# Smart_Assistant.net
KiCad netlist of a schematic drawn in Altium Designer
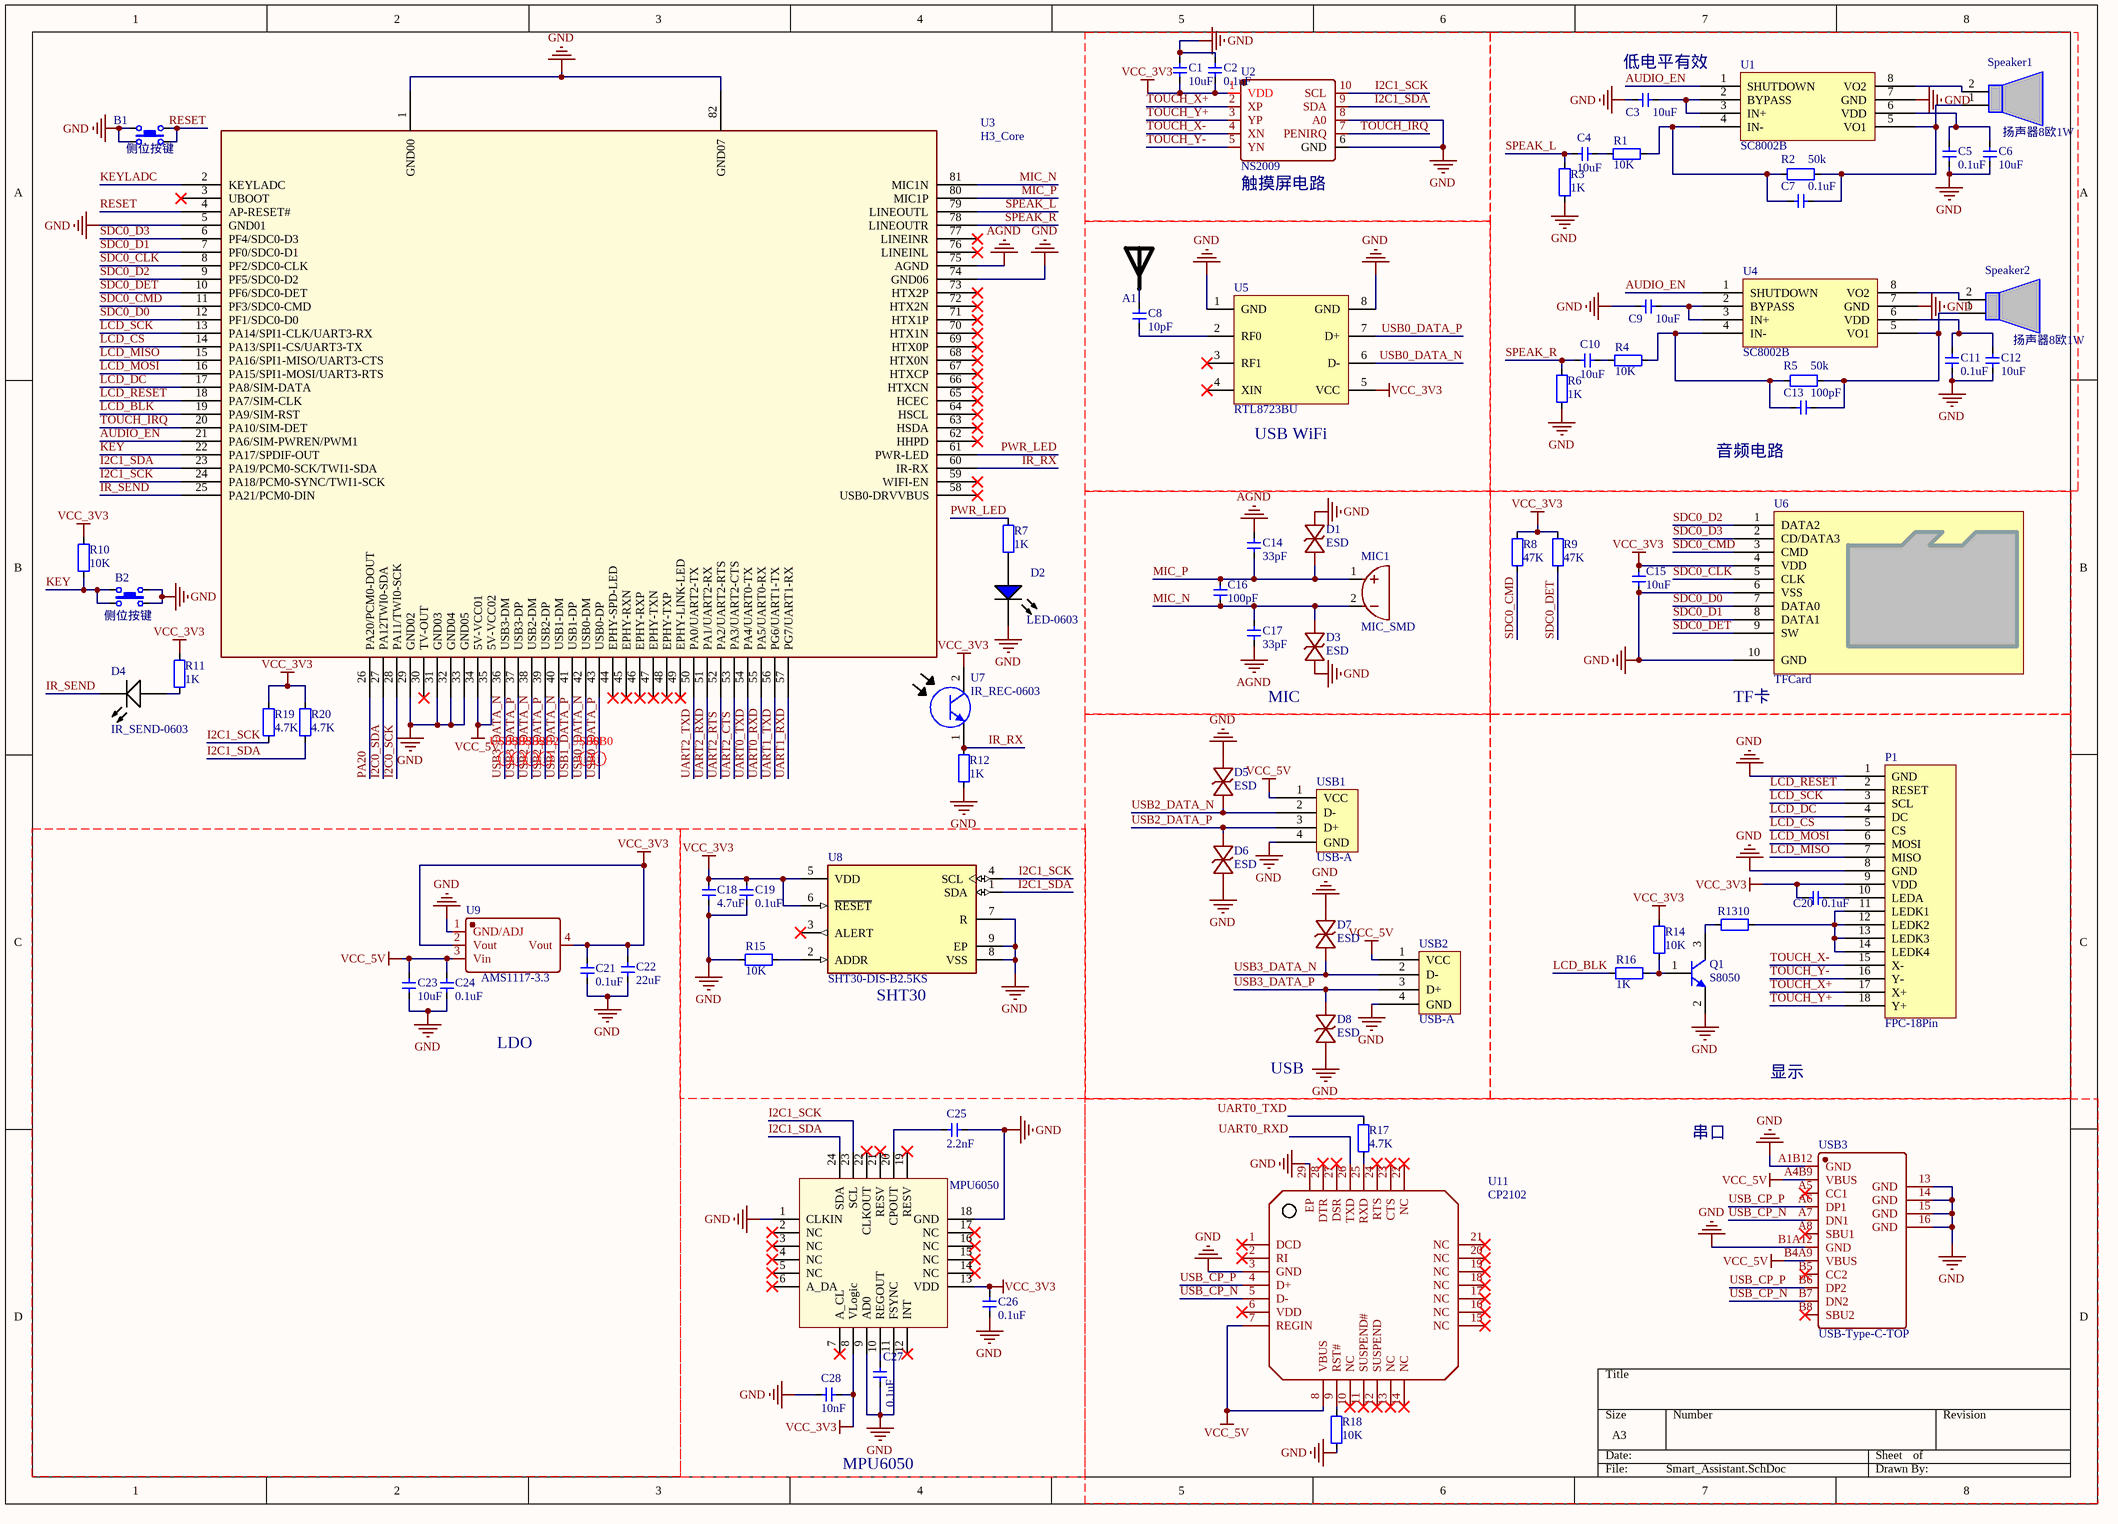
[diagram p0: Smart_Assistant.SchDoc]

(export (version "E")
  (design (tool "Eeschema 10.0.6"))
  (components
    (comp (ref "A1")
      (value "RAINSUN")
      (footprint "ANT-Rainsun-AN5120")
      (description "陶瓷天线")
      (libsource (lib "My_Library") (part "ANT-Rainsun-AP5120"))
    )
    (comp (ref "B1")
      (value "侧位按键")
      (footprint "侧位按键_3.5*3.55_90")
      (libsource (lib "My_Library") (part "侧位按键"))
    )
    (comp (ref "B2")
      (value "侧位按键")
      (footprint "侧位按键_3.5*3.55_90")
      (libsource (lib "My_Library") (part "侧位按键"))
    )
    (comp (ref "C1")
      (value "10uF")
      (footprint "电容0603")
      (description "Capacitor")
      (libsource (lib "My_Library") (part "电容-0603"))
    )
    (comp (ref "C2")
      (value "0.1uF")
      (footprint "电容0603")
      (description "Capacitor")
      (libsource (lib "My_Library") (part "电容-0603"))
    )
    (comp (ref "C3")
      (value "10uF")
      (footprint "电容0603")
      (description "Capacitor")
      (libsource (lib "My_Library") (part "电容-0603"))
    )
    (comp (ref "C4")
      (value "10uF")
      (footprint "电容0603")
      (description "Capacitor")
      (libsource (lib "My_Library") (part "电容-0603"))
    )
    (comp (ref "C5")
      (value "0.1uF")
      (footprint "电容0603")
      (description "Capacitor")
      (libsource (lib "My_Library") (part "电容-0603"))
    )
    (comp (ref "C6")
      (value "10uF")
      (footprint "电容0603")
      (description "Capacitor")
      (libsource (lib "My_Library") (part "电容-0603"))
    )
    (comp (ref "C7")
      (value "0.1uF")
      (footprint "电容0603")
      (description "Capacitor")
      (libsource (lib "My_Library") (part "电容-0603"))
    )
    (comp (ref "C8")
      (value "10pF")
      (footprint "电容0603")
      (description "Capacitor")
      (libsource (lib "My_Library") (part "电容-0603"))
    )
    (comp (ref "C9")
      (value "10uF")
      (footprint "电容0603")
      (description "Capacitor")
      (libsource (lib "My_Library") (part "电容-0603"))
    )
    (comp (ref "C10")
      (value "10uF")
      (footprint "电容0603")
      (description "Capacitor")
      (libsource (lib "My_Library") (part "电容-0603"))
    )
    (comp (ref "C11")
      (value "0.1uF")
      (footprint "电容0603")
      (description "Capacitor")
      (libsource (lib "My_Library") (part "电容-0603"))
    )
    (comp (ref "C12")
      (value "10uF")
      (footprint "电容0603")
      (description "Capacitor")
      (libsource (lib "My_Library") (part "电容-0603"))
    )
    (comp (ref "C13")
      (value "100pF")
      (footprint "电容0603")
      (description "Capacitor")
      (libsource (lib "My_Library") (part "电容-0603"))
    )
    (comp (ref "C14")
      (value "33pF")
      (footprint "电容0603")
      (description "Capacitor")
      (libsource (lib "My_Library") (part "电容-0603"))
    )
    (comp (ref "C15")
      (value "10uF")
      (footprint "电容0603")
      (description "Capacitor")
      (libsource (lib "My_Library") (part "电容-0603"))
    )
    (comp (ref "C16")
      (value "100pF")
      (footprint "电容0603")
      (description "Capacitor")
      (libsource (lib "My_Library") (part "电容-0603"))
    )
    (comp (ref "C17")
      (value "33pF")
      (footprint "电容0603")
      (description "Capacitor")
      (libsource (lib "My_Library") (part "电容-0603"))
    )
    (comp (ref "C18")
      (value "4.7uF")
      (footprint "电容0603")
      (description "Capacitor")
      (libsource (lib "My_Library") (part "电容-0603"))
    )
    (comp (ref "C19")
      (value "0.1uF")
      (footprint "电容0603")
      (description "Capacitor")
      (libsource (lib "My_Library") (part "电容-0603"))
    )
    (comp (ref "C20")
      (value "0.1uF")
      (footprint "电容0603")
      (description "Capacitor")
      (libsource (lib "My_Library") (part "电容-0603"))
    )
    (comp (ref "C21")
      (value "0.1uF")
      (footprint "电容0603")
      (description "Capacitor")
      (libsource (lib "My_Library") (part "电容-0603"))
    )
    (comp (ref "C22")
      (value "22uF")
      (footprint "电容0603")
      (description "Capacitor")
      (libsource (lib "My_Library") (part "电容-0603"))
    )
    (comp (ref "C23")
      (value "10uF")
      (footprint "电容0603")
      (description "Capacitor")
      (libsource (lib "My_Library") (part "电容-0603"))
    )
    (comp (ref "C24")
      (value "0.1uF")
      (footprint "电容0603")
      (description "Capacitor")
      (libsource (lib "My_Library") (part "电容-0603"))
    )
    (comp (ref "C25")
      (value "2.2nF")
      (footprint "电容0603")
      (description "Capacitor")
      (libsource (lib "My_Library") (part "电容-0603"))
    )
    (comp (ref "C26")
      (value "0.1uF")
      (footprint "电容0603")
      (description "Capacitor")
      (libsource (lib "My_Library") (part "电容-0603"))
    )
    (comp (ref "C27")
      (value "0.1uF")
      (footprint "电容0603")
      (description "Capacitor")
      (libsource (lib "My_Library") (part "电容-0603"))
    )
    (comp (ref "C28")
      (value "10nF")
      (footprint "电容0603")
      (description "Capacitor")
      (libsource (lib "My_Library") (part "电容-0603"))
    )
    (comp (ref "D1") (value "ESD") (footprint "ESD-0603") (libsource (lib "My_Library") (part "ESD-0603")))
    (comp (ref "D2")
      (value "LED-0603")
      (footprint "LED-0603")
      (libsource (lib "My_Library") (part "LED-0603"))
    )
    (comp (ref "D3") (value "ESD") (footprint "ESD-0603") (libsource (lib "My_Library") (part "ESD-0603")))
    (comp (ref "D4")
      (value "IR_SEND-0603")
      (footprint "IR_SEND-0603")
      (description "红外发射管")
      (libsource (lib "My_Library") (part "IR_SEND-0603"))
    )
    (comp (ref "D5") (value "ESD") (footprint "ESD-0603") (libsource (lib "My_Library") (part "ESD-0603")))
    (comp (ref "D6") (value "ESD") (footprint "ESD-0603") (libsource (lib "My_Library") (part "ESD-0603")))
    (comp (ref "D7") (value "ESD") (footprint "ESD-0603") (libsource (lib "My_Library") (part "ESD-0603")))
    (comp (ref "D8") (value "ESD") (footprint "ESD-0603") (libsource (lib "My_Library") (part "ESD-0603")))
    (comp (ref "MIC1")
      (value "MIC_SMD")
      (footprint "MIC_SMD")
      (libsource (lib "My_Library") (part "MIC_SMD"))
    )
    (comp (ref "P1")
      (value "FPC-18Pin")
      (footprint "FPC-0.5mm-18Pin")
      (description "2.4寸LCD 中景园")
      (libsource (lib "My_Library") (part "FPC-18Pin"))
    )
    (comp (ref "Q1")
      (value "S8050")
      (footprint "NPN-SOT-23")
      (description "High Voltage Transistor, NPN Silicon, 3-Pin SOT-23, Pb-Free, Tape and Reel")
      (fields (field (name "PARTNUMBER") "MMBTA42LT1G") (field (name "MANUFACTURER") "On Semiconductor"))
      (libsource (lib "My_Library") (part "贴片NPN三极管"))
    )
    (comp (ref "R1")
      (value "10K")
      (footprint "电阻0603")
      (description "Resistor")
      (libsource (lib "") (part "电阻-0603_1"))
    )
    (comp (ref "R2")
      (value "50k")
      (footprint "电阻0603")
      (description "Resistor")
      (libsource (lib "") (part "电阻-0603_1"))
    )
    (comp (ref "R3")
      (value "1K")
      (footprint "电阻0603")
      (description "Resistor")
      (libsource (lib "My_Library") (part "电阻-0603"))
    )
    (comp (ref "R4")
      (value "10K")
      (footprint "电阻0603")
      (description "Resistor")
      (libsource (lib "") (part "电阻-0603_1"))
    )
    (comp (ref "R5")
      (value "50k")
      (footprint "电阻0603")
      (description "Resistor")
      (libsource (lib "") (part "电阻-0603_1"))
    )
    (comp (ref "R6")
      (value "1K")
      (footprint "电阻0603")
      (description "Resistor")
      (libsource (lib "My_Library") (part "电阻-0603"))
    )
    (comp (ref "R7")
      (value "1K")
      (footprint "电阻0603")
      (description "Resistor")
      (libsource (lib "") (part "电阻-0603_2"))
    )
    (comp (ref "R8")
      (value "47K")
      (footprint "电阻0603")
      (description "Resistor")
      (libsource (lib "") (part "电阻-0603_2"))
    )
    (comp (ref "R9")
      (value "47K")
      (footprint "电阻0603")
      (description "Resistor")
      (libsource (lib "") (part "电阻-0603_2"))
    )
    (comp (ref "R10")
      (value "10K")
      (footprint "电阻0603")
      (description "Resistor")
      (libsource (lib "My_Library") (part "电阻-0603"))
    )
    (comp (ref "R11")
      (value "1K")
      (footprint "电阻0603")
      (description "Resistor")
      (libsource (lib "My_Library") (part "电阻-0603"))
    )
    (comp (ref "R12")
      (value "1K")
      (footprint "电阻0603")
      (description "Resistor")
      (libsource (lib "") (part "电阻-0603_2"))
    )
    (comp (ref "R13")
      (value "10")
      (footprint "电阻0603")
      (description "Resistor")
      (libsource (lib "") (part "电阻-0603_1"))
    )
    (comp (ref "R14")
      (value "10K")
      (footprint "电阻0603")
      (description "Resistor")
      (libsource (lib "My_Library") (part "电阻-0603"))
    )
    (comp (ref "R15")
      (value "10K")
      (footprint "电阻0603")
      (description "Resistor")
      (libsource (lib "") (part "电阻-0603_1"))
    )
    (comp (ref "R16")
      (value "1K")
      (footprint "电阻0603")
      (description "Resistor")
      (libsource (lib "") (part "电阻-0603_1"))
    )
    (comp (ref "R17")
      (value "4.7K")
      (footprint "电阻0603")
      (description "Resistor")
      (libsource (lib "My_Library") (part "电阻-0603"))
    )
    (comp (ref "R18")
      (value "10K")
      (footprint "电阻0603")
      (description "Resistor")
      (libsource (lib "My_Library") (part "电阻-0603"))
    )
    (comp (ref "R19")
      (value "4.7K")
      (footprint "电阻0603")
      (description "Resistor")
      (libsource (lib "My_Library") (part "电阻-0603"))
    )
    (comp (ref "R20")
      (value "4.7K")
      (footprint "电阻0603")
      (description "Resistor")
      (libsource (lib "My_Library") (part "电阻-0603"))
    )
    (comp (ref "Speaker1")
      (value "扬声器8欧1W")
      (footprint "扬声器 8欧1W")
      (libsource (lib "My_Library") (part "扬声器8欧1W"))
    )
    (comp (ref "Speaker2")
      (value "扬声器8欧1W")
      (footprint "扬声器 8欧1W")
      (libsource (lib "My_Library") (part "扬声器8欧1W"))
    )
    (comp (ref "U1")
      (value "SC8002B")
      (footprint "SC8002B-SOP-8")
      (description "单声道4欧姆2.5W输出音频放大器")
      (libsource (lib "My_Library") (part "SC8002B"))
    )
    (comp (ref "U2") (value "NS2009") (footprint "NS2009") (libsource (lib "My_Library") (part "NS2009")))
    (comp (ref "U3")
      (value "H3_Core")
      (footprint "H3_Core")
      (description "Allwinner_H3核心板 40.8mm*32mm 82pin")
      (libsource (lib "My_Library") (part "H3_Core"))
    )
    (comp (ref "U4")
      (value "SC8002B")
      (footprint "SC8002B-SOP-8")
      (description "单声道4欧姆2.5W输出音频放大器")
      (libsource (lib "My_Library") (part "SC8002B"))
    )
    (comp (ref "U5")
      (value "RTL8723BU")
      (footprint "UBS_WiFi")
      (libsource (lib "My_Library") (part "USB_WiFi"))
    )
    (comp (ref "U6") (value "TFCard") (footprint "TFCard") (libsource (lib "My_Library") (part "TFCard")))
    (comp (ref "U7")
      (value "IR_REC-0603")
      (footprint "IR_REC-0603")
      (description "红外接收管")
      (libsource (lib "My_Library") (part "IR_REC-0603"))
    )
    (comp (ref "U8")
      (value "SHT30-DIS-B2.5KS")
      (footprint "FP-SHT30-DIS-B2_5KS-MFG")
      (description "SHT30 I2C地址为0x44")
      (fields (field (name "MANUFACTURER") "Sensirion"))
      (libsource (lib "My_Library") (part "SHT30"))
    )
    (comp (ref "U9")
      (value "AMS1117-3.3")
      (footprint "AMS1117-3.3")
      (description "5V-3.3V 1A")
      (libsource (lib "My_Library") (part "AMS1117-3.3 SOT-23"))
    )
    (comp (ref "U10")
      (value "MPU6050")
      (footprint "QFN24-4*4")
      (description "六轴传感器")
      (libsource (lib "My_Library") (part "MPU6050"))
    )
    (comp (ref "U11") (value "CP2102") (footprint "CP2102") (libsource (lib "My_Library") (part "CP2102")))
    (comp (ref "USB1") (value "USB-A") (footprint "USB-A-TOP") (libsource (lib "My_Library") (part "USB-A")))
    (comp (ref "USB2") (value "USB-A") (footprint "USB-A-TOP") (libsource (lib "My_Library") (part "USB-A")))
    (comp (ref "USB3")
      (value "USB-Type-C-TOP")
      (footprint "Type-C-TOP")
      (libsource (lib "My_Library") (part "USB-Type-C-TOP"))
    )
  )
  (nets
    (net (code "1") (name "/AUDIO_EN") (class "Default")
      (node (ref "U1") (pin "1") (pinfunction "SHUTDOWN_1") (pintype "passive"))
      (node (ref "U3") (pin "21") (pinfunction "PA6/SIM-PWREN/PWM1_21") (pintype "passive"))
      (node (ref "U4") (pin "1") (pinfunction "SHUTDOWN_1") (pintype "passive"))
    )
    (net (code "2") (name "/I2C0_SCK") (class "Default")
      (node (ref "U3") (pin "28") (pinfunction "PA11/TWI0-SCK_28") (pintype "passive"))
    )
    (net (code "3") (name "/I2C0_SDA") (class "Default")
      (node (ref "U3") (pin "27") (pinfunction "PA12TWI0-SDA_27") (pintype "passive"))
    )
    (net (code "4") (name "/I2C1_SCK") (class "Default")
      (node (ref "R19") (pin "1") (pinfunction "1_1") (pintype "passive"))
      (node (ref "U10") (pin "23") (pinfunction "SCL_23") (pintype "passive"))
      (node (ref "U2") (pin "10") (pinfunction "SCL_10") (pintype "passive"))
      (node (ref "U3") (pin "24") (pinfunction "PA18/PCM0-SYNC/TWI1-SCK_24") (pintype "passive"))
      (node (ref "U8") (pin "4") (pinfunction "SCL_4") (pintype "bidirectional"))
    )
    (net (code "5") (name "/I2C1_SDA") (class "Default")
      (node (ref "R20") (pin "1") (pinfunction "1_1") (pintype "passive"))
      (node (ref "U10") (pin "24") (pinfunction "SDA_24") (pintype "passive"))
      (node (ref "U2") (pin "9") (pinfunction "SDA_9") (pintype "passive"))
      (node (ref "U3") (pin "23") (pinfunction "PA19/PCM0-SCK/TWI1-SDA_23") (pintype "passive"))
      (node (ref "U8") (pin "1") (pinfunction "SDA_1") (pintype "bidirectional"))
    )
    (net (code "6") (name "/IR_RX") (class "Default")
      (node (ref "R12") (pin "1") (pinfunction "1_1") (pintype "passive"))
      (node (ref "U3") (pin "60") (pinfunction "IR-RX_60") (pintype "passive"))
      (node (ref "U7") (pin "1") (pinfunction "E_1") (pintype "passive"))
    )
    (net (code "7") (name "/IR_SEND") (class "Default")
      (node (ref "D4") (pin "2") (pinfunction "K_2") (pintype "passive"))
      (node (ref "U3") (pin "25") (pinfunction "PA21/PCM0-DIN_25") (pintype "passive"))
    )
    (net (code "8") (name "/KEY") (class "Default")
      (node (ref "B2") (pin "1") (pinfunction "1_1") (pintype "passive"))
      (node (ref "B2") (pin "3") (pinfunction "3_3") (pintype "passive"))
      (node (ref "R10") (pin "1") (pinfunction "1_1") (pintype "passive"))
      (node (ref "U3") (pin "22") (pinfunction "PA17/SPDIF-OUT_22") (pintype "passive"))
    )
    (net (code "9") (name "/KEYLADC") (class "Default")
      (node (ref "U3") (pin "2") (pinfunction "KEYLADC_2") (pintype "passive"))
    )
    (net (code "10") (name "/LCD_BLK") (class "Default")
      (node (ref "R16") (pin "1") (pinfunction "1_1") (pintype "passive"))
      (node (ref "U3") (pin "19") (pinfunction "PA9/SIM-RST_19") (pintype "passive"))
    )
    (net (code "11") (name "/LCD_CS") (class "Default")
      (node (ref "P1") (pin "5") (pinfunction "CS_5") (pintype "passive"))
      (node (ref "U3") (pin "14") (pinfunction "PA13/SPI1-CS/UART3-TX_14") (pintype "passive"))
    )
    (net (code "12") (name "/LCD_DC") (class "Default")
      (node (ref "P1") (pin "4") (pinfunction "DC_4") (pintype "passive"))
      (node (ref "U3") (pin "17") (pinfunction "PA8/SIM-DATA_17") (pintype "passive"))
    )
    (net (code "13") (name "/LCD_MISO") (class "Default")
      (node (ref "P1") (pin "7") (pinfunction "MISO_7") (pintype "passive"))
      (node (ref "U3") (pin "15") (pinfunction "PA16/SPI1-MISO/UART3-CTS_15") (pintype "passive"))
    )
    (net (code "14") (name "/LCD_MOSI") (class "Default")
      (node (ref "P1") (pin "6") (pinfunction "MOSI_6") (pintype "passive"))
      (node (ref "U3") (pin "16") (pinfunction "PA15/SPI1-MOSI/UART3-RTS_16") (pintype "passive"))
    )
    (net (code "15") (name "/LCD_RESET") (class "Default")
      (node (ref "P1") (pin "2") (pinfunction "RESET_2") (pintype "passive"))
      (node (ref "U3") (pin "18") (pinfunction "PA7/SIM-CLK_18") (pintype "passive"))
    )
    (net (code "16") (name "/LCD_SCK") (class "Default")
      (node (ref "P1") (pin "3") (pinfunction "SCL_3") (pintype "passive"))
      (node (ref "U3") (pin "13") (pinfunction "PA14/SPI1-CLK/UART3-RX_13") (pintype "passive"))
    )
    (net (code "17") (name "/MIC_N") (class "Default")
      (node (ref "C16") (pin "1") (pinfunction "1_1") (pintype "passive"))
      (node (ref "C17") (pin "2") (pinfunction "2_2") (pintype "passive"))
      (node (ref "D3") (pin "2") (pinfunction "2_2") (pintype "passive"))
      (node (ref "MIC1") (pin "2") (pinfunction "2_2") (pintype "passive"))
      (node (ref "U3") (pin "81") (pinfunction "MIC1N_81") (pintype "passive"))
    )
    (net (code "18") (name "/MIC_P") (class "Default")
      (node (ref "C14") (pin "1") (pinfunction "1_1") (pintype "passive"))
      (node (ref "C16") (pin "2") (pinfunction "2_2") (pintype "passive"))
      (node (ref "D1") (pin "1") (pinfunction "1_1") (pintype "passive"))
      (node (ref "MIC1") (pin "1") (pinfunction "1_1") (pintype "passive"))
      (node (ref "U3") (pin "80") (pinfunction "MIC1P_80") (pintype "passive"))
    )
    (net (code "19") (name "/PA20") (class "Default")
      (node (ref "U3") (pin "26") (pinfunction "PA20/PCM0-DOUT_26") (pintype "passive"))
    )
    (net (code "20") (name "/PWR_LED") (class "Default")
      (node (ref "R7") (pin "1") (pinfunction "1_1") (pintype "passive"))
      (node (ref "U3") (pin "61") (pinfunction "PWR-LED_61") (pintype "passive"))
    )
    (net (code "21") (name "/RESET") (class "Default")
      (node (ref "B1") (pin "2") (pinfunction "2_2") (pintype "passive"))
      (node (ref "B1") (pin "4") (pinfunction "4_4") (pintype "passive"))
      (node (ref "U3") (pin "4") (pinfunction "AP-RESET#_4") (pintype "passive"))
    )
    (net (code "22") (name "/SDC0_CLK") (class "Default")
      (node (ref "U3") (pin "8") (pinfunction "PF2/SDC0-CLK_8") (pintype "passive"))
      (node (ref "U6") (pin "5") (pinfunction "CLK_5") (pintype "passive"))
    )
    (net (code "23") (name "/SDC0_CMD") (class "Default")
      (node (ref "R8") (pin "2") (pinfunction "2_2") (pintype "passive"))
      (node (ref "U3") (pin "11") (pinfunction "PF3/SDC0-CMD_11") (pintype "passive"))
      (node (ref "U6") (pin "3") (pinfunction "CMD_3") (pintype "passive"))
    )
    (net (code "24") (name "/SDC0_D0") (class "Default")
      (node (ref "U3") (pin "12") (pinfunction "PF1/SDC0-D0_12") (pintype "passive"))
      (node (ref "U6") (pin "7") (pinfunction "DATA0_7") (pintype "passive"))
    )
    (net (code "25") (name "/SDC0_D1") (class "Default")
      (node (ref "U3") (pin "7") (pinfunction "PF0/SDC0-D1_7") (pintype "passive"))
      (node (ref "U6") (pin "8") (pinfunction "DATA1_8") (pintype "passive"))
    )
    (net (code "26") (name "/SDC0_D2") (class "Default")
      (node (ref "U3") (pin "9") (pinfunction "PF5/SDC0-D2_9") (pintype "passive"))
      (node (ref "U6") (pin "1") (pinfunction "DATA2_1") (pintype "passive"))
    )
    (net (code "27") (name "/SDC0_D3") (class "Default")
      (node (ref "U3") (pin "6") (pinfunction "PF4/SDC0-D3_6") (pintype "passive"))
      (node (ref "U6") (pin "2") (pinfunction "CD/DATA3_2") (pintype "passive"))
    )
    (net (code "28") (name "/SDC0_DET") (class "Default")
      (node (ref "R9") (pin "2") (pinfunction "2_2") (pintype "passive"))
      (node (ref "U3") (pin "10") (pinfunction "PF6/SDC0-DET_10") (pintype "passive"))
      (node (ref "U6") (pin "9") (pinfunction "SW_9") (pintype "passive"))
    )
    (net (code "29") (name "/SPEAK_L") (class "Default")
      (node (ref "C4") (pin "2") (pinfunction "2_2") (pintype "passive"))
      (node (ref "R3") (pin "2") (pinfunction "2_2") (pintype "passive"))
      (node (ref "U3") (pin "79") (pinfunction "LINEOUTL_79") (pintype "passive"))
    )
    (net (code "30") (name "/SPEAK_R") (class "Default")
      (node (ref "C10") (pin "2") (pinfunction "2_2") (pintype "passive"))
      (node (ref "R6") (pin "2") (pinfunction "2_2") (pintype "passive"))
      (node (ref "U3") (pin "78") (pinfunction "LINEOUTR_78") (pintype "passive"))
    )
    (net (code "31") (name "/TOUCH_IRQ") (class "Default")
      (node (ref "U2") (pin "7") (pinfunction "PENIRQ_7") (pintype "passive"))
      (node (ref "U3") (pin "20") (pinfunction "PA10/SIM-DET_20") (pintype "passive"))
    )
    (net (code "32") (name "/TOUCH_X+") (class "Default")
      (node (ref "P1") (pin "17") (pinfunction "X+_17") (pintype "passive"))
      (node (ref "U2") (pin "2") (pinfunction "XP_2") (pintype "passive"))
    )
    (net (code "33") (name "/TOUCH_X-") (class "Default")
      (node (ref "P1") (pin "15") (pinfunction "X-_15") (pintype "passive"))
      (node (ref "U2") (pin "4") (pinfunction "XN_4") (pintype "passive"))
    )
    (net (code "34") (name "/TOUCH_Y+") (class "Default")
      (node (ref "P1") (pin "18") (pinfunction "Y+_18") (pintype "passive"))
      (node (ref "U2") (pin "3") (pinfunction "YP_3") (pintype "passive"))
    )
    (net (code "35") (name "/TOUCH_Y-") (class "Default")
      (node (ref "P1") (pin "16") (pinfunction "Y-_16") (pintype "passive"))
      (node (ref "U2") (pin "5") (pinfunction "YN_5") (pintype "passive"))
    )
    (net (code "36") (name "/UART0_RXD") (class "Default")
      (node (ref "U11") (pin "26") (pinfunction "TXD_26") (pintype "passive"))
      (node (ref "U3") (pin "55") (pinfunction "PA5/UART0-RX_55") (pintype "passive"))
    )
    (net (code "37") (name "/UART0_TXD") (class "Default")
      (node (ref "R17") (pin "2") (pinfunction "2_2") (pintype "passive"))
      (node (ref "U3") (pin "54") (pinfunction "PA4/UART0-TX_54") (pintype "passive"))
    )
    (net (code "38") (name "/UART1_RXD") (class "Default")
      (node (ref "U3") (pin "57") (pinfunction "PG7/UART1-RX_57") (pintype "passive"))
    )
    (net (code "39") (name "/UART1_TXD") (class "Default")
      (node (ref "U3") (pin "56") (pinfunction "PG6/UART1-TX_56") (pintype "passive"))
    )
    (net (code "40") (name "/UART2_CTS") (class "Default")
      (node (ref "U3") (pin "53") (pinfunction "PA3/UART2-CTS_53") (pintype "passive"))
    )
    (net (code "41") (name "/UART2_RTS") (class "Default")
      (node (ref "U3") (pin "52") (pinfunction "PA2/UART2-RTS_52") (pintype "passive"))
    )
    (net (code "42") (name "/UART2_RXD") (class "Default")
      (node (ref "U3") (pin "51") (pinfunction "PA1/UART2-RX_51") (pintype "passive"))
    )
    (net (code "43") (name "/UART2_TXD") (class "Default")
      (node (ref "U3") (pin "50") (pinfunction "PA0/UART2-TX_50") (pintype "passive"))
    )
    (net (code "44") (name "/USB0_DATA_N") (class "Default")
      (node (ref "U3") (pin "42") (pinfunction "USB0-DM_42") (pintype "passive"))
      (node (ref "U5") (pin "6") (pinfunction "D-_6") (pintype "passive"))
    )
    (net (code "45") (name "/USB0_DATA_P") (class "Default")
      (node (ref "U3") (pin "43") (pinfunction "USB0-DP_43") (pintype "passive"))
      (node (ref "U5") (pin "7") (pinfunction "D+_7") (pintype "passive"))
    )
    (net (code "46") (name "/USB1_DATA_N") (class "Default")
      (node (ref "U3") (pin "40") (pinfunction "USB1-DM_40") (pintype "passive"))
    )
    (net (code "47") (name "/USB1_DATA_P") (class "Default")
      (node (ref "U3") (pin "41") (pinfunction "USB1-DP_41") (pintype "passive"))
    )
    (net (code "48") (name "/USB2_DATA_N") (class "Default")
      (node (ref "D5") (pin "1") (pinfunction "1_1") (pintype "passive"))
      (node (ref "U3") (pin "38") (pinfunction "USB2-DM_38") (pintype "passive"))
      (node (ref "USB1") (pin "2") (pinfunction "D-_2") (pintype "passive"))
    )
    (net (code "49") (name "/USB2_DATA_P") (class "Default")
      (node (ref "D6") (pin "2") (pinfunction "2_2") (pintype "passive"))
      (node (ref "U3") (pin "39") (pinfunction "USB2-DP_39") (pintype "passive"))
      (node (ref "USB1") (pin "3") (pinfunction "D+_3") (pintype "passive"))
    )
    (net (code "50") (name "/USB3_DATA_N") (class "Default")
      (node (ref "D7") (pin "1") (pinfunction "1_1") (pintype "passive"))
      (node (ref "U3") (pin "36") (pinfunction "USB3-DM_36") (pintype "passive"))
      (node (ref "USB2") (pin "2") (pinfunction "D-_2") (pintype "passive"))
    )
    (net (code "51") (name "/USB3_DATA_P") (class "Default")
      (node (ref "D8") (pin "2") (pinfunction "2_2") (pintype "passive"))
      (node (ref "U3") (pin "37") (pinfunction "USB3-DP_37") (pintype "passive"))
      (node (ref "USB2") (pin "3") (pinfunction "D+_3") (pintype "passive"))
    )
    (net (code "52") (name "/USB_CP_N") (class "Default")
      (node (ref "U11") (pin "5") (pinfunction "D-_5") (pintype "passive"))
      (node (ref "USB3") (pin "A7") (pinfunction "DN1_A7") (pintype "passive"))
      (node (ref "USB3") (pin "B7") (pinfunction "DN2_B7") (pintype "passive"))
    )
    (net (code "53") (name "/USB_CP_P") (class "Default")
      (node (ref "U11") (pin "4") (pinfunction "D+_4") (pintype "passive"))
      (node (ref "USB3") (pin "A6") (pinfunction "DP1_A6") (pintype "passive"))
      (node (ref "USB3") (pin "B6") (pinfunction "DP2_B6") (pintype "passive"))
    )
    (net (code "54") (name "AGND") (class "Default")
      (node (ref "C14") (pin "2") (pinfunction "2_2") (pintype "passive"))
      (node (ref "C17") (pin "1") (pinfunction "1_1") (pintype "passive"))
      (node (ref "U3") (pin "75") (pinfunction "AGND_75") (pintype "passive"))
    )
    (net (code "55") (name "GND") (class "Default")
      (node (ref "B1") (pin "1") (pinfunction "1_1") (pintype "passive"))
      (node (ref "B1") (pin "3") (pinfunction "3_3") (pintype "passive"))
      (node (ref "B2") (pin "2") (pinfunction "2_2") (pintype "passive"))
      (node (ref "B2") (pin "4") (pinfunction "4_4") (pintype "passive"))
      (node (ref "C1") (pin "2") (pinfunction "2_2") (pintype "passive"))
      (node (ref "C11") (pin "1") (pinfunction "1_1") (pintype "passive"))
      (node (ref "C12") (pin "1") (pinfunction "1_1") (pintype "passive"))
      (node (ref "C15") (pin "1") (pinfunction "1_1") (pintype "passive"))
      (node (ref "C18") (pin "1") (pinfunction "1_1") (pintype "passive"))
      (node (ref "C19") (pin "1") (pinfunction "1_1") (pintype "passive"))
      (node (ref "C2") (pin "2") (pinfunction "2_2") (pintype "passive"))
      (node (ref "C21") (pin "1") (pinfunction "1_1") (pintype "passive"))
      (node (ref "C22") (pin "1") (pinfunction "1_1") (pintype "passive"))
      (node (ref "C23") (pin "1") (pinfunction "1_1") (pintype "passive"))
      (node (ref "C24") (pin "1") (pinfunction "1_1") (pintype "passive"))
      (node (ref "C25") (pin "2") (pinfunction "2_2") (pintype "passive"))
      (node (ref "C26") (pin "1") (pinfunction "1_1") (pintype "passive"))
      (node (ref "C27") (pin "1") (pinfunction "1_1") (pintype "passive"))
      (node (ref "C28") (pin "1") (pinfunction "1_1") (pintype "passive"))
      (node (ref "C3") (pin "1") (pinfunction "1_1") (pintype "passive"))
      (node (ref "C5") (pin "1") (pinfunction "1_1") (pintype "passive"))
      (node (ref "C6") (pin "1") (pinfunction "1_1") (pintype "passive"))
      (node (ref "C9") (pin "1") (pinfunction "1_1") (pintype "passive"))
      (node (ref "D1") (pin "2") (pinfunction "2_2") (pintype "passive"))
      (node (ref "D2") (pin "2") (pinfunction "K_2") (pintype "passive"))
      (node (ref "D3") (pin "1") (pinfunction "1_1") (pintype "passive"))
      (node (ref "D5") (pin "2") (pinfunction "2_2") (pintype "passive"))
      (node (ref "D6") (pin "1") (pinfunction "1_1") (pintype "passive"))
      (node (ref "D7") (pin "2") (pinfunction "2_2") (pintype "passive"))
      (node (ref "D8") (pin "1") (pinfunction "1_1") (pintype "passive"))
      (node (ref "P1") (pin "1") (pinfunction "GND_1") (pintype "passive"))
      (node (ref "P1") (pin "8") (pinfunction "GND_8") (pintype "passive"))
      (node (ref "Q1") (pin "2") (pinfunction "E_2") (pintype "passive"))
      (node (ref "R12") (pin "2") (pinfunction "2_2") (pintype "passive"))
      (node (ref "R15") (pin "1") (pinfunction "1_1") (pintype "passive"))
      (node (ref "R18") (pin "1") (pinfunction "1_1") (pintype "passive"))
      (node (ref "R3") (pin "1") (pinfunction "1_1") (pintype "passive"))
      (node (ref "R6") (pin "1") (pinfunction "1_1") (pintype "passive"))
      (node (ref "U1") (pin "7") (pinfunction "GND_7") (pintype "passive"))
      (node (ref "U10") (pin "1") (pinfunction "CLKIN_1") (pintype "passive"))
      (node (ref "U10") (pin "11") (pinfunction "FSYNC_11") (pintype "passive"))
      (node (ref "U10") (pin "18") (pinfunction "GND_18") (pintype "passive"))
      (node (ref "U10") (pin "9") (pinfunction "AD0_9") (pintype "passive"))
      (node (ref "U11") (pin "29") (pinfunction "EP_29") (pintype "passive"))
      (node (ref "U11") (pin "3") (pinfunction "GND_3") (pintype "passive"))
      (node (ref "U2") (pin "6") (pinfunction "GND_6") (pintype "passive"))
      (node (ref "U2") (pin "8") (pinfunction "A0_8") (pintype "passive"))
      (node (ref "U3") (pin "1") (pinfunction "GND00_1") (pintype "passive"))
      (node (ref "U3") (pin "29") (pinfunction "GND02_29") (pintype "passive"))
      (node (ref "U3") (pin "31") (pinfunction "GND03_31") (pintype "passive"))
      (node (ref "U3") (pin "32") (pinfunction "GND04_32") (pintype "passive"))
      (node (ref "U3") (pin "33") (pinfunction "GND05_33") (pintype "passive"))
      (node (ref "U3") (pin "5") (pinfunction "GND01_5") (pintype "passive"))
      (node (ref "U3") (pin "74") (pinfunction "GND06_74") (pintype "passive"))
      (node (ref "U3") (pin "82") (pinfunction "GND07_82") (pintype "passive"))
      (node (ref "U4") (pin "7") (pinfunction "GND_7") (pintype "passive"))
      (node (ref "U5") (pin "1") (pinfunction "GND_1") (pintype "passive"))
      (node (ref "U5") (pin "8") (pinfunction "GND_8") (pintype "passive"))
      (node (ref "U6") (pin "10") (pinfunction "GND_10") (pintype "passive"))
      (node (ref "U6") (pin "6") (pinfunction "VSS_6") (pintype "passive"))
      (node (ref "U8") (pin "7") (pinfunction "R_7") (pintype "passive"))
      (node (ref "U8") (pin "8") (pinfunction "VSS_8") (pintype "power_in"))
      (node (ref "U8") (pin "9") (pinfunction "EP_9") (pintype "passive"))
      (node (ref "U9") (pin "1") (pinfunction "GND/ADJ_1") (pintype "passive"))
      (node (ref "USB1") (pin "4") (pinfunction "GND_4") (pintype "passive"))
      (node (ref "USB2") (pin "4") (pinfunction "GND_4") (pintype "passive"))
      (node (ref "USB3") (pin "13") (pinfunction "GND_13") (pintype "passive"))
      (node (ref "USB3") (pin "14") (pinfunction "GND_14") (pintype "passive"))
      (node (ref "USB3") (pin "15") (pinfunction "GND_15") (pintype "passive"))
      (node (ref "USB3") (pin "16") (pinfunction "GND_16") (pintype "passive"))
      (node (ref "USB3") (pin "A1B12") (pinfunction "GND_A1B12") (pintype "passive"))
      (node (ref "USB3") (pin "B1A12") (pinfunction "GND_B1A12") (pintype "passive"))
    )
    (net (code "56") (name "Net-(A1-Pad1)") (class "Default")
      (node (ref "A1") (pin "1") (pinfunction "1_1") (pintype "passive"))
      (node (ref "C8") (pin "2") (pinfunction "2_2") (pintype "passive"))
    )
    (net (code "57") (name "Net-(C4-Pad1)") (class "Default")
      (node (ref "C4") (pin "1") (pinfunction "1_1") (pintype "passive"))
      (node (ref "R1") (pin "1") (pinfunction "1_1") (pintype "passive"))
    )
    (net (code "58") (name "Net-(C10-Pad1)") (class "Default")
      (node (ref "C10") (pin "1") (pinfunction "1_1") (pintype "passive"))
      (node (ref "R4") (pin "1") (pinfunction "1_1") (pintype "passive"))
    )
    (net (code "59") (name "Net-(D2-A)") (class "Default")
      (node (ref "D2") (pin "1") (pinfunction "A_1") (pintype "passive"))
      (node (ref "R7") (pin "2") (pinfunction "2_2") (pintype "passive"))
    )
    (net (code "60") (name "Net-(D4-A)") (class "Default")
      (node (ref "D4") (pin "1") (pinfunction "A_1") (pintype "passive"))
      (node (ref "R11") (pin "1") (pinfunction "1_1") (pintype "passive"))
    )
    (net (code "61") (name "Net-(P1-LEDA)") (class "Default")
      (node (ref "C20") (pin "2") (pinfunction "2_2") (pintype "passive"))
      (node (ref "P1") (pin "10") (pinfunction "LEDA_10") (pintype "passive"))
    )
    (net (code "62") (name "Net-(P1-LEDK1)") (class "Default")
      (node (ref "P1") (pin "11") (pinfunction "LEDK1_11") (pintype "passive"))
      (node (ref "P1") (pin "12") (pinfunction "LEDK2_12") (pintype "passive"))
      (node (ref "P1") (pin "13") (pinfunction "LEDK3_13") (pintype "passive"))
      (node (ref "P1") (pin "14") (pinfunction "LEDK4_14") (pintype "passive"))
      (node (ref "R13") (pin "2") (pinfunction "2_2") (pintype "passive"))
    )
    (net (code "63") (name "Net-(Q1-B)") (class "Default")
      (node (ref "Q1") (pin "1") (pinfunction "B_1") (pintype "passive"))
      (node (ref "R14") (pin "1") (pinfunction "1_1") (pintype "passive"))
      (node (ref "R16") (pin "2") (pinfunction "2_2") (pintype "passive"))
    )
    (net (code "64") (name "Net-(Q1-C)") (class "Default")
      (node (ref "Q1") (pin "3") (pinfunction "C_3") (pintype "passive"))
      (node (ref "R13") (pin "1") (pinfunction "1_1") (pintype "passive"))
    )
    (net (code "65") (name "Net-(U1-BYPASS)") (class "Default")
      (node (ref "C3") (pin "2") (pinfunction "2_2") (pintype "passive"))
      (node (ref "U1") (pin "2") (pinfunction "BYPASS_2") (pintype "passive"))
      (node (ref "U1") (pin "3") (pinfunction "IN+_3") (pintype "passive"))
    )
    (net (code "66") (name "Net-(U1-IN-)") (class "Default")
      (node (ref "C7") (pin "1") (pinfunction "1_1") (pintype "passive"))
      (node (ref "R1") (pin "2") (pinfunction "2_2") (pintype "passive"))
      (node (ref "R2") (pin "1") (pinfunction "1_1") (pintype "passive"))
      (node (ref "U1") (pin "4") (pinfunction "IN-_4") (pintype "passive"))
    )
    (net (code "67") (name "Net-(U1-VDD)") (class "Default")
      (node (ref "C5") (pin "2") (pinfunction "2_2") (pintype "passive"))
      (node (ref "C6") (pin "2") (pinfunction "2_2") (pintype "passive"))
      (node (ref "U1") (pin "6") (pinfunction "VDD_6") (pintype "passive"))
    )
    (net (code "68") (name "Net-(U1-VO1)") (class "Default")
      (node (ref "C7") (pin "2") (pinfunction "2_2") (pintype "passive"))
      (node (ref "R2") (pin "2") (pinfunction "2_2") (pintype "passive"))
      (node (ref "Speaker1") (pin "1") (pintype "passive"))
      (node (ref "U1") (pin "5") (pinfunction "VO1_5") (pintype "passive"))
    )
    (net (code "69") (name "Net-(U1-VO2)") (class "Default")
      (node (ref "Speaker1") (pin "2") (pintype "passive"))
      (node (ref "U1") (pin "8") (pinfunction "VO2_8") (pintype "passive"))
    )
    (net (code "70") (name "Net-(U4-BYPASS)") (class "Default")
      (node (ref "C9") (pin "2") (pinfunction "2_2") (pintype "passive"))
      (node (ref "U4") (pin "2") (pinfunction "BYPASS_2") (pintype "passive"))
      (node (ref "U4") (pin "3") (pinfunction "IN+_3") (pintype "passive"))
    )
    (net (code "71") (name "Net-(U4-IN-)") (class "Default")
      (node (ref "C13") (pin "1") (pinfunction "1_1") (pintype "passive"))
      (node (ref "R4") (pin "2") (pinfunction "2_2") (pintype "passive"))
      (node (ref "R5") (pin "1") (pinfunction "1_1") (pintype "passive"))
      (node (ref "U4") (pin "4") (pinfunction "IN-_4") (pintype "passive"))
    )
    (net (code "72") (name "Net-(U4-VDD)") (class "Default")
      (node (ref "C11") (pin "2") (pinfunction "2_2") (pintype "passive"))
      (node (ref "C12") (pin "2") (pinfunction "2_2") (pintype "passive"))
      (node (ref "U4") (pin "6") (pinfunction "VDD_6") (pintype "passive"))
    )
    (net (code "73") (name "Net-(U4-VO1)") (class "Default")
      (node (ref "C13") (pin "2") (pinfunction "2_2") (pintype "passive"))
      (node (ref "R5") (pin "2") (pinfunction "2_2") (pintype "passive"))
      (node (ref "Speaker2") (pin "1") (pintype "passive"))
      (node (ref "U4") (pin "5") (pinfunction "VO1_5") (pintype "passive"))
    )
    (net (code "74") (name "Net-(U4-VO2)") (class "Default")
      (node (ref "Speaker2") (pin "2") (pintype "passive"))
      (node (ref "U4") (pin "8") (pinfunction "VO2_8") (pintype "passive"))
    )
    (net (code "75") (name "Net-(U5-RF0)") (class "Default")
      (node (ref "C8") (pin "1") (pinfunction "1_1") (pintype "passive"))
      (node (ref "U5") (pin "2") (pinfunction "RF0_2") (pintype "passive"))
    )
    (net (code "76") (name "Net-(U8-ADDR)") (class "Default")
      (node (ref "R15") (pin "2") (pinfunction "2_2") (pintype "passive"))
      (node (ref "U8") (pin "2") (pinfunction "ADDR_2") (pintype "input"))
    )
    (net (code "77") (name "Net-(U10-CPOUT)") (class "Default")
      (node (ref "C25") (pin "1") (pinfunction "1_1") (pintype "passive"))
      (node (ref "U10") (pin "20") (pinfunction "CPOUT_20") (pintype "passive"))
    )
    (net (code "78") (name "Net-(U10-REGOUT)") (class "Default")
      (node (ref "C27") (pin "2") (pinfunction "2_2") (pintype "passive"))
      (node (ref "U10") (pin "10") (pinfunction "REGOUT_10") (pintype "passive"))
    )
    (net (code "79") (name "Net-(U11-RST#)") (class "Default")
      (node (ref "R18") (pin "2") (pinfunction "2_2") (pintype "passive"))
      (node (ref "U11") (pin "9") (pinfunction "RST#_9") (pintype "passive"))
    )
    (net (code "80") (name "Net-(U11-RXD)") (class "Default")
      (node (ref "R17") (pin "1") (pinfunction "1_1") (pintype "passive"))
      (node (ref "U11") (pin "25") (pinfunction "RXD_25") (pintype "passive"))
    )
    (net (code "81") (name "VCC_3V3") (class "Default")
      (node (ref "C1") (pin "1") (pinfunction "1_1") (pintype "passive"))
      (node (ref "C15") (pin "2") (pinfunction "2_2") (pintype "passive"))
      (node (ref "C18") (pin "2") (pinfunction "2_2") (pintype "passive"))
      (node (ref "C19") (pin "2") (pinfunction "2_2") (pintype "passive"))
      (node (ref "C2") (pin "1") (pinfunction "1_1") (pintype "passive"))
      (node (ref "C20") (pin "1") (pinfunction "1_1") (pintype "passive"))
      (node (ref "C21") (pin "2") (pinfunction "2_2") (pintype "passive"))
      (node (ref "C22") (pin "2") (pinfunction "2_2") (pintype "passive"))
      (node (ref "C26") (pin "2") (pinfunction "2_2") (pintype "passive"))
      (node (ref "C28") (pin "2") (pinfunction "2_2") (pintype "passive"))
      (node (ref "P1") (pin "9") (pinfunction "VDD_9") (pintype "passive"))
      (node (ref "R10") (pin "2") (pinfunction "2_2") (pintype "passive"))
      (node (ref "R11") (pin "2") (pinfunction "2_2") (pintype "passive"))
      (node (ref "R14") (pin "2") (pinfunction "2_2") (pintype "passive"))
      (node (ref "R19") (pin "2") (pinfunction "2_2") (pintype "passive"))
      (node (ref "R20") (pin "2") (pinfunction "2_2") (pintype "passive"))
      (node (ref "R8") (pin "1") (pinfunction "1_1") (pintype "passive"))
      (node (ref "R9") (pin "1") (pinfunction "1_1") (pintype "passive"))
      (node (ref "U10") (pin "13") (pinfunction "VDD_13") (pintype "passive"))
      (node (ref "U10") (pin "8") (pinfunction "VLogic_8") (pintype "passive"))
      (node (ref "U2") (pin "1") (pinfunction "VDD_1") (pintype "passive"))
      (node (ref "U5") (pin "5") (pinfunction "VCC_5") (pintype "passive"))
      (node (ref "U6") (pin "4") (pinfunction "VDD_4") (pintype "passive"))
      (node (ref "U7") (pin "2") (pinfunction "C_2") (pintype "passive"))
      (node (ref "U8") (pin "5") (pinfunction "VDD_5") (pintype "power_in"))
      (node (ref "U8") (pin "6") (pinfunction "~{RESET}_6") (pintype "input"))
      (node (ref "U9") (pin "2") (pinfunction "Vout_2") (pintype "passive"))
      (node (ref "U9") (pin "4") (pinfunction "Vout_4") (pintype "passive"))
    )
    (net (code "82") (name "VCC_5V") (class "Default")
      (node (ref "C23") (pin "2") (pinfunction "2_2") (pintype "passive"))
      (node (ref "C24") (pin "2") (pinfunction "2_2") (pintype "passive"))
      (node (ref "U11") (pin "7") (pinfunction "REGIN_7") (pintype "passive"))
      (node (ref "U11") (pin "8") (pinfunction "VBUS_8") (pintype "passive"))
      (node (ref "U3") (pin "34") (pinfunction "5V-VCC01_34") (pintype "passive"))
      (node (ref "U3") (pin "35") (pinfunction "5V-VCC02_35") (pintype "passive"))
      (node (ref "U9") (pin "3") (pinfunction "Vin_3") (pintype "passive"))
      (node (ref "USB1") (pin "1") (pinfunction "VCC_1") (pintype "passive"))
      (node (ref "USB2") (pin "1") (pinfunction "VCC_1") (pintype "passive"))
      (node (ref "USB3") (pin "A4B9") (pinfunction "VBUS_A4B9") (pintype "passive"))
      (node (ref "USB3") (pin "B4A9") (pinfunction "VBUS_B4A9") (pintype "passive"))
    )
    (net (code "83") (name "unconnected-(U3-EPHY-LINK-LED-Pad49)") (class "Default")
      (node (ref "U3") (pin "49") (pinfunction "EPHY-LINK-LED_49") (pintype "passive+no_connect"))
    )
    (net (code "84") (name "unconnected-(U3-EPHY-RXN-Pad45)") (class "Default")
      (node (ref "U3") (pin "45") (pinfunction "EPHY-RXN_45") (pintype "passive+no_connect"))
    )
    (net (code "85") (name "unconnected-(U3-EPHY-RXP-Pad46)") (class "Default")
      (node (ref "U3") (pin "46") (pinfunction "EPHY-RXP_46") (pintype "passive+no_connect"))
    )
    (net (code "86") (name "unconnected-(U3-EPHY-SPD-LED-Pad44)") (class "Default")
      (node (ref "U3") (pin "44") (pinfunction "EPHY-SPD-LED_44") (pintype "passive+no_connect"))
    )
    (net (code "87") (name "unconnected-(U3-EPHY-TXN-Pad47)") (class "Default")
      (node (ref "U3") (pin "47") (pinfunction "EPHY-TXN_47") (pintype "passive+no_connect"))
    )
    (net (code "88") (name "unconnected-(U3-EPHY-TXP-Pad48)") (class "Default")
      (node (ref "U3") (pin "48") (pinfunction "EPHY-TXP_48") (pintype "passive+no_connect"))
    )
    (net (code "89") (name "unconnected-(U3-HCEC-Pad65)") (class "Default")
      (node (ref "U3") (pin "65") (pinfunction "HCEC_65") (pintype "passive+no_connect"))
    )
    (net (code "90") (name "unconnected-(U3-HHPD-Pad62)") (class "Default")
      (node (ref "U3") (pin "62") (pinfunction "HHPD_62") (pintype "passive+no_connect"))
    )
    (net (code "91") (name "unconnected-(U3-HSCL-Pad64)") (class "Default")
      (node (ref "U3") (pin "64") (pinfunction "HSCL_64") (pintype "passive+no_connect"))
    )
    (net (code "92") (name "unconnected-(U3-HSDA-Pad63)") (class "Default")
      (node (ref "U3") (pin "63") (pinfunction "HSDA_63") (pintype "passive+no_connect"))
    )
    (net (code "93") (name "unconnected-(U3-HTX0N-Pad68)") (class "Default")
      (node (ref "U3") (pin "68") (pinfunction "HTX0N_68") (pintype "passive+no_connect"))
    )
    (net (code "94") (name "unconnected-(U3-HTX0P-Pad69)") (class "Default")
      (node (ref "U3") (pin "69") (pinfunction "HTX0P_69") (pintype "passive+no_connect"))
    )
    (net (code "95") (name "unconnected-(U3-HTX1N-Pad70)") (class "Default")
      (node (ref "U3") (pin "70") (pinfunction "HTX1N_70") (pintype "passive+no_connect"))
    )
    (net (code "96") (name "unconnected-(U3-HTX1P-Pad71)") (class "Default")
      (node (ref "U3") (pin "71") (pinfunction "HTX1P_71") (pintype "passive+no_connect"))
    )
    (net (code "97") (name "unconnected-(U3-HTX2N-Pad72)") (class "Default")
      (node (ref "U3") (pin "72") (pinfunction "HTX2N_72") (pintype "passive+no_connect"))
    )
    (net (code "98") (name "unconnected-(U3-HTX2P-Pad73)") (class "Default")
      (node (ref "U3") (pin "73") (pinfunction "HTX2P_73") (pintype "passive+no_connect"))
    )
    (net (code "99") (name "unconnected-(U3-HTXCN-Pad66)") (class "Default")
      (node (ref "U3") (pin "66") (pinfunction "HTXCN_66") (pintype "passive+no_connect"))
    )
    (net (code "100") (name "unconnected-(U3-HTXCP-Pad67)") (class "Default")
      (node (ref "U3") (pin "67") (pinfunction "HTXCP_67") (pintype "passive+no_connect"))
    )
    (net (code "101") (name "unconnected-(U3-LINEINL-Pad76)") (class "Default")
      (node (ref "U3") (pin "76") (pinfunction "LINEINL_76") (pintype "passive+no_connect"))
    )
    (net (code "102") (name "unconnected-(U3-LINEINR-Pad77)") (class "Default")
      (node (ref "U3") (pin "77") (pinfunction "LINEINR_77") (pintype "passive+no_connect"))
    )
    (net (code "103") (name "unconnected-(U3-TV-OUT-Pad30)") (class "Default")
      (node (ref "U3") (pin "30") (pinfunction "TV-OUT_30") (pintype "passive+no_connect"))
    )
    (net (code "104") (name "unconnected-(U3-UBOOT-Pad3)") (class "Default")
      (node (ref "U3") (pin "3") (pinfunction "UBOOT_3") (pintype "passive+no_connect"))
    )
    (net (code "105") (name "unconnected-(U3-USB0-DRVVBUS-Pad58)") (class "Default")
      (node (ref "U3") (pin "58") (pinfunction "USB0-DRVVBUS_58") (pintype "passive+no_connect"))
    )
    (net (code "106") (name "unconnected-(U3-WIFI-EN-Pad59)") (class "Default")
      (node (ref "U3") (pin "59") (pinfunction "WIFI-EN_59") (pintype "passive+no_connect"))
    )
    (net (code "107") (name "unconnected-(U5-RF1-Pad3)") (class "Default")
      (node (ref "U5") (pin "3") (pinfunction "RF1_3") (pintype "passive+no_connect"))
    )
    (net (code "108") (name "unconnected-(U5-XIN-Pad4)") (class "Default")
      (node (ref "U5") (pin "4") (pinfunction "XIN_4") (pintype "passive+no_connect"))
    )
    (net (code "109") (name "unconnected-(U8-ALERT-Pad3)") (class "Default")
      (node (ref "U8") (pin "3") (pinfunction "ALERT_3") (pintype "output+no_connect"))
    )
    (net (code "110") (name "unconnected-(U10-A_CL-Pad7)") (class "Default")
      (node (ref "U10") (pin "7") (pinfunction "A_CL_7") (pintype "passive+no_connect"))
    )
    (net (code "111") (name "unconnected-(U10-A_DA-Pad6)") (class "Default")
      (node (ref "U10") (pin "6") (pinfunction "A_DA_6") (pintype "passive+no_connect"))
    )
    (net (code "112") (name "unconnected-(U10-CLKOUT-Pad22)") (class "Default")
      (node (ref "U10") (pin "22") (pinfunction "CLKOUT_22") (pintype "passive+no_connect"))
    )
    (net (code "113") (name "unconnected-(U10-INT-Pad12)") (class "Default")
      (node (ref "U10") (pin "12") (pinfunction "INT_12") (pintype "passive+no_connect"))
    )
    (net (code "114") (name "unconnected-(U10-NC-Pad2)") (class "Default")
      (node (ref "U10") (pin "2") (pinfunction "NC_2") (pintype "passive+no_connect"))
    )
    (net (code "115") (name "unconnected-(U10-NC-Pad3)") (class "Default")
      (node (ref "U10") (pin "3") (pinfunction "NC_3") (pintype "passive+no_connect"))
    )
    (net (code "116") (name "unconnected-(U10-NC-Pad4)") (class "Default")
      (node (ref "U10") (pin "4") (pinfunction "NC_4") (pintype "passive+no_connect"))
    )
    (net (code "117") (name "unconnected-(U10-NC-Pad5)") (class "Default")
      (node (ref "U10") (pin "5") (pinfunction "NC_5") (pintype "passive+no_connect"))
    )
    (net (code "118") (name "unconnected-(U10-NC-Pad14)") (class "Default")
      (node (ref "U10") (pin "14") (pinfunction "NC_14") (pintype "passive+no_connect"))
    )
    (net (code "119") (name "unconnected-(U10-NC-Pad15)") (class "Default")
      (node (ref "U10") (pin "15") (pinfunction "NC_15") (pintype "passive+no_connect"))
    )
    (net (code "120") (name "unconnected-(U10-NC-Pad16)") (class "Default")
      (node (ref "U10") (pin "16") (pinfunction "NC_16") (pintype "passive+no_connect"))
    )
    (net (code "121") (name "unconnected-(U10-NC-Pad17)") (class "Default")
      (node (ref "U10") (pin "17") (pinfunction "NC_17") (pintype "passive+no_connect"))
    )
    (net (code "122") (name "unconnected-(U10-RESV-Pad19)") (class "Default")
      (node (ref "U10") (pin "19") (pinfunction "RESV_19") (pintype "passive+no_connect"))
    )
    (net (code "123") (name "unconnected-(U10-RESV-Pad21)") (class "Default")
      (node (ref "U10") (pin "21") (pinfunction "RESV_21") (pintype "passive+no_connect"))
    )
    (net (code "124") (name "unconnected-(U11-CTS-Pad23)") (class "Default")
      (node (ref "U11") (pin "23") (pinfunction "CTS_23") (pintype "passive+no_connect"))
    )
    (net (code "125") (name "unconnected-(U11-DCD-Pad1)") (class "Default")
      (node (ref "U11") (pin "1") (pinfunction "DCD_1") (pintype "passive+no_connect"))
    )
    (net (code "126") (name "unconnected-(U11-DSR-Pad27)") (class "Default")
      (node (ref "U11") (pin "27") (pinfunction "DSR_27") (pintype "passive+no_connect"))
    )
    (net (code "127") (name "unconnected-(U11-DTR-Pad28)") (class "Default")
      (node (ref "U11") (pin "28") (pinfunction "DTR_28") (pintype "passive+no_connect"))
    )
    (net (code "128") (name "unconnected-(U11-NC-Pad10)") (class "Default")
      (node (ref "U11") (pin "10") (pinfunction "NC_10") (pintype "passive+no_connect"))
    )
    (net (code "129") (name "unconnected-(U11-NC-Pad13)") (class "Default")
      (node (ref "U11") (pin "13") (pinfunction "NC_13") (pintype "passive+no_connect"))
    )
    (net (code "130") (name "unconnected-(U11-NC-Pad14)") (class "Default")
      (node (ref "U11") (pin "14") (pinfunction "NC_14") (pintype "passive+no_connect"))
    )
    (net (code "131") (name "unconnected-(U11-NC-Pad15)") (class "Default")
      (node (ref "U11") (pin "15") (pinfunction "NC_15") (pintype "passive+no_connect"))
    )
    (net (code "132") (name "unconnected-(U11-NC-Pad16)") (class "Default")
      (node (ref "U11") (pin "16") (pinfunction "NC_16") (pintype "passive+no_connect"))
    )
    (net (code "133") (name "unconnected-(U11-NC-Pad17)") (class "Default")
      (node (ref "U11") (pin "17") (pinfunction "NC_17") (pintype "passive+no_connect"))
    )
    (net (code "134") (name "unconnected-(U11-NC-Pad18)") (class "Default")
      (node (ref "U11") (pin "18") (pinfunction "NC_18") (pintype "passive+no_connect"))
    )
    (net (code "135") (name "unconnected-(U11-NC-Pad19)") (class "Default")
      (node (ref "U11") (pin "19") (pinfunction "NC_19") (pintype "passive+no_connect"))
    )
    (net (code "136") (name "unconnected-(U11-NC-Pad20)") (class "Default")
      (node (ref "U11") (pin "20") (pinfunction "NC_20") (pintype "passive+no_connect"))
    )
    (net (code "137") (name "unconnected-(U11-NC-Pad21)") (class "Default")
      (node (ref "U11") (pin "21") (pinfunction "NC_21") (pintype "passive+no_connect"))
    )
    (net (code "138") (name "unconnected-(U11-NC-Pad22)") (class "Default")
      (node (ref "U11") (pin "22") (pinfunction "NC_22") (pintype "passive+no_connect"))
    )
    (net (code "139") (name "unconnected-(U11-RI-Pad2)") (class "Default")
      (node (ref "U11") (pin "2") (pinfunction "RI_2") (pintype "passive+no_connect"))
    )
    (net (code "140") (name "unconnected-(U11-RTS-Pad24)") (class "Default")
      (node (ref "U11") (pin "24") (pinfunction "RTS_24") (pintype "passive+no_connect"))
    )
    (net (code "141") (name "unconnected-(U11-SUSPEND#-Pad11)") (class "Default")
      (node (ref "U11") (pin "11") (pinfunction "SUSPEND#_11") (pintype "passive+no_connect"))
    )
    (net (code "142") (name "unconnected-(U11-SUSPEND-Pad12)") (class "Default")
      (node (ref "U11") (pin "12") (pinfunction "SUSPEND_12") (pintype "passive+no_connect"))
    )
    (net (code "143") (name "unconnected-(U11-VDD-Pad6)") (class "Default")
      (node (ref "U11") (pin "6") (pinfunction "VDD_6") (pintype "passive+no_connect"))
    )
    (net (code "144") (name "unconnected-(USB3-CC1-PadA5)") (class "Default")
      (node (ref "USB3") (pin "A5") (pinfunction "CC1_A5") (pintype "passive+no_connect"))
    )
    (net (code "145") (name "unconnected-(USB3-CC2-PadB5)") (class "Default")
      (node (ref "USB3") (pin "B5") (pinfunction "CC2_B5") (pintype "passive+no_connect"))
    )
    (net (code "146") (name "unconnected-(USB3-SBU1-PadA8)") (class "Default")
      (node (ref "USB3") (pin "A8") (pinfunction "SBU1_A8") (pintype "passive+no_connect"))
    )
    (net (code "147") (name "unconnected-(USB3-SBU2-PadB8)") (class "Default")
      (node (ref "USB3") (pin "B8") (pinfunction "SBU2_B8") (pintype "passive+no_connect"))
    )
  )
)
